# InputDig.net
KiCad netlist of a schematic drawn in Altium Designer
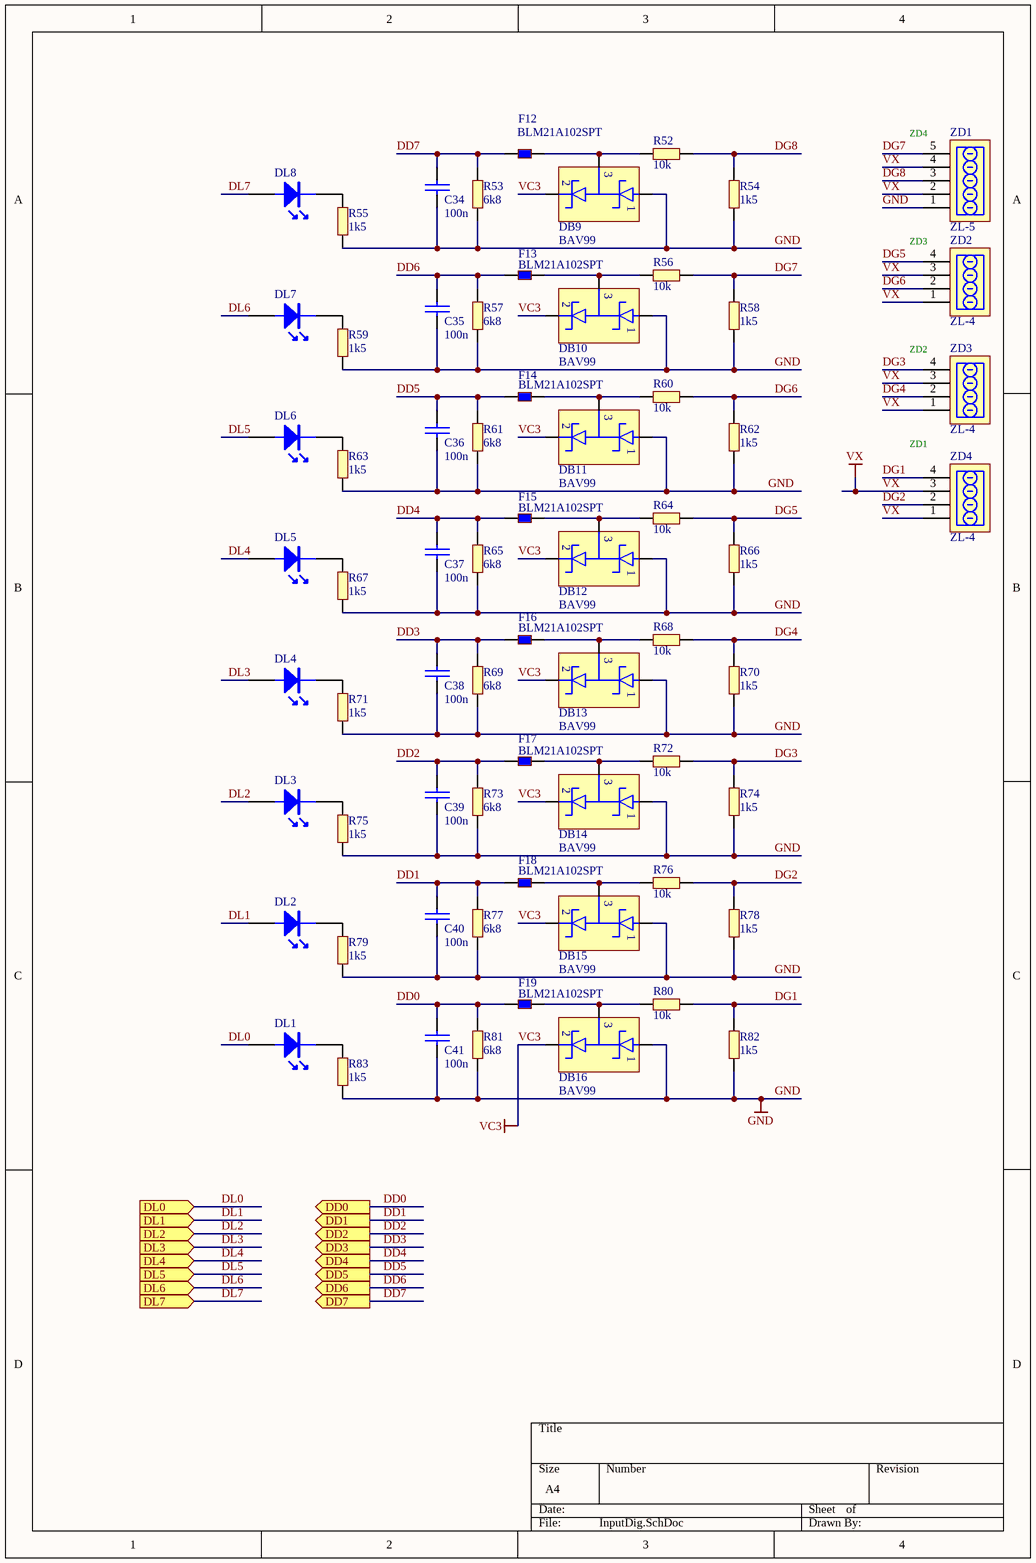
[diagram p0: InputDig.SchDoc]

(export (version "E")
  (design (tool "Eeschema 10.0.6"))
  (components
    (comp (ref "C34")
      (value "100n")
      (footprint "0603C")
      (description "Capacitor")
      (libsource (lib "*") (part "CAP"))
    )
    (comp (ref "C35")
      (value "100n")
      (footprint "0603C")
      (description "Capacitor")
      (libsource (lib "*") (part "CAP"))
    )
    (comp (ref "C36")
      (value "100n")
      (footprint "0603C")
      (description "Capacitor")
      (libsource (lib "*") (part "CAP"))
    )
    (comp (ref "C37")
      (value "100n")
      (footprint "0603C")
      (description "Capacitor")
      (libsource (lib "*") (part "CAP"))
    )
    (comp (ref "C38")
      (value "100n")
      (footprint "0603C")
      (description "Capacitor")
      (libsource (lib "*") (part "CAP"))
    )
    (comp (ref "C39")
      (value "100n")
      (footprint "0603C")
      (description "Capacitor")
      (libsource (lib "*") (part "CAP"))
    )
    (comp (ref "C40")
      (value "100n")
      (footprint "0603C")
      (description "Capacitor")
      (libsource (lib "*") (part "CAP"))
    )
    (comp (ref "C41")
      (value "100n")
      (footprint "0603C")
      (description "Capacitor")
      (libsource (lib "*") (part "CAP"))
    )
    (comp (ref "DB9") (value "BAV99") (footprint "SOT-23") (libsource (lib "*") (part "BAS70-04")))
    (comp (ref "DB10") (value "BAV99") (footprint "SOT-23") (libsource (lib "*") (part "BAS70-04")))
    (comp (ref "DB11") (value "BAV99") (footprint "SOT-23") (libsource (lib "*") (part "BAS70-04")))
    (comp (ref "DB12") (value "BAV99") (footprint "SOT-23") (libsource (lib "*") (part "BAS70-04")))
    (comp (ref "DB13") (value "BAV99") (footprint "SOT-23") (libsource (lib "*") (part "BAS70-04")))
    (comp (ref "DB14") (value "BAV99") (footprint "SOT-23") (libsource (lib "*") (part "BAS70-04")))
    (comp (ref "DB15") (value "BAV99") (footprint "SOT-23") (libsource (lib "*") (part "BAS70-04")))
    (comp (ref "DB16") (value "BAV99") (footprint "SOT-23") (libsource (lib "*") (part "BAS70-04")))
    (comp (ref "DL1") (value "~") (footprint "0603DR") (libsource (lib "*") (part "LED")))
    (comp (ref "DL2") (value "~") (footprint "0603DR") (libsource (lib "*") (part "LED")))
    (comp (ref "DL3") (value "~") (footprint "0603DR") (libsource (lib "*") (part "LED")))
    (comp (ref "DL4") (value "~") (footprint "0603DR") (libsource (lib "*") (part "LED")))
    (comp (ref "DL5") (value "~") (footprint "0603DR") (libsource (lib "*") (part "LED")))
    (comp (ref "DL6") (value "~") (footprint "0603DR") (libsource (lib "*") (part "LED")))
    (comp (ref "DL7") (value "~") (footprint "0603DR") (libsource (lib "*") (part "LED")))
    (comp (ref "DL8") (value "~") (footprint "0603DR") (libsource (lib "*") (part "LED")))
    (comp (ref "F12")
      (value "BLM21A102SPT")
      (footprint "0603L")
      (description "Koralik ferrytowy")
      (libsource (lib "*") (part "KORALIK"))
    )
    (comp (ref "F13")
      (value "BLM21A102SPT")
      (footprint "0603L")
      (description "Koralik ferrytowy")
      (libsource (lib "*") (part "KORALIK"))
    )
    (comp (ref "F14")
      (value "BLM21A102SPT")
      (footprint "0603L")
      (description "Koralik ferrytowy")
      (libsource (lib "*") (part "KORALIK"))
    )
    (comp (ref "F15")
      (value "BLM21A102SPT")
      (footprint "0603L")
      (description "Koralik ferrytowy")
      (libsource (lib "*") (part "KORALIK"))
    )
    (comp (ref "F16")
      (value "BLM21A102SPT")
      (footprint "0603L")
      (description "Koralik ferrytowy")
      (libsource (lib "*") (part "KORALIK"))
    )
    (comp (ref "F17")
      (value "BLM21A102SPT")
      (footprint "0603L")
      (description "Koralik ferrytowy")
      (libsource (lib "*") (part "KORALIK"))
    )
    (comp (ref "F18")
      (value "BLM21A102SPT")
      (footprint "0603L")
      (description "Koralik ferrytowy")
      (libsource (lib "*") (part "KORALIK"))
    )
    (comp (ref "F19")
      (value "BLM21A102SPT")
      (footprint "0603L")
      (description "Koralik ferrytowy")
      (libsource (lib "*") (part "KORALIK"))
    )
    (comp (ref "R52") (value "10k") (footprint "0603R") (libsource (lib "*") (part "RES3")))
    (comp (ref "R53") (value "6k8") (footprint "0603R") (libsource (lib "") (part "RES3_1")))
    (comp (ref "R54") (value "1k5") (footprint "0805R") (libsource (lib "*") (part "RES3")))
    (comp (ref "R55") (value "1k5") (footprint "0603R") (libsource (lib "*") (part "RES3")))
    (comp (ref "R56") (value "10k") (footprint "0603R") (libsource (lib "*") (part "RES3")))
    (comp (ref "R57") (value "6k8") (footprint "0603R") (libsource (lib "") (part "RES3_1")))
    (comp (ref "R58") (value "1k5") (footprint "0805R") (libsource (lib "*") (part "RES3")))
    (comp (ref "R59") (value "1k5") (footprint "0603R") (libsource (lib "*") (part "RES3")))
    (comp (ref "R60") (value "10k") (footprint "0603R") (libsource (lib "*") (part "RES3")))
    (comp (ref "R61") (value "6k8") (footprint "0603R") (libsource (lib "") (part "RES3_1")))
    (comp (ref "R62") (value "1k5") (footprint "0805R") (libsource (lib "*") (part "RES3")))
    (comp (ref "R63") (value "1k5") (footprint "0603R") (libsource (lib "*") (part "RES3")))
    (comp (ref "R64") (value "10k") (footprint "0603R") (libsource (lib "*") (part "RES3")))
    (comp (ref "R65") (value "6k8") (footprint "0603R") (libsource (lib "") (part "RES3_1")))
    (comp (ref "R66") (value "1k5") (footprint "0805R") (libsource (lib "*") (part "RES3")))
    (comp (ref "R67") (value "1k5") (footprint "0603R") (libsource (lib "*") (part "RES3")))
    (comp (ref "R68") (value "10k") (footprint "0603R") (libsource (lib "*") (part "RES3")))
    (comp (ref "R69") (value "6k8") (footprint "0603R") (libsource (lib "") (part "RES3_1")))
    (comp (ref "R70") (value "1k5") (footprint "0805R") (libsource (lib "*") (part "RES3")))
    (comp (ref "R71") (value "1k5") (footprint "0603R") (libsource (lib "*") (part "RES3")))
    (comp (ref "R72") (value "10k") (footprint "0603R") (libsource (lib "*") (part "RES3")))
    (comp (ref "R73") (value "6k8") (footprint "0603R") (libsource (lib "") (part "RES3_1")))
    (comp (ref "R74") (value "1k5") (footprint "0805R") (libsource (lib "*") (part "RES3")))
    (comp (ref "R75") (value "1k5") (footprint "0603R") (libsource (lib "*") (part "RES3")))
    (comp (ref "R76") (value "10k") (footprint "0603R") (libsource (lib "*") (part "RES3")))
    (comp (ref "R77") (value "6k8") (footprint "0603R") (libsource (lib "") (part "RES3_1")))
    (comp (ref "R78") (value "1k5") (footprint "0805R") (libsource (lib "*") (part "RES3")))
    (comp (ref "R79") (value "1k5") (footprint "0603R") (libsource (lib "*") (part "RES3")))
    (comp (ref "R80") (value "10k") (footprint "0603R") (libsource (lib "*") (part "RES3")))
    (comp (ref "R81") (value "6k8") (footprint "0603R") (libsource (lib "") (part "RES3_1")))
    (comp (ref "R82") (value "1k5") (footprint "0805R") (libsource (lib "*") (part "RES3")))
    (comp (ref "R83") (value "1k5") (footprint "0603R") (libsource (lib "*") (part "RES3")))
    (comp (ref "ZD1")
      (value "ZL-5")
      (footprint "ARC-5-3.5-TYCO-2")
      (libsource (lib "ElhosSchLib") (part "ZL-5"))
    )
    (comp (ref "ZD2") (value "ZL-4") (footprint "ARC-4-3.5-TYCO-2") (libsource (lib "*") (part "ZL-4")))
    (comp (ref "ZD3") (value "ZL-4") (footprint "ARC-4-3.5-TYCO-2") (libsource (lib "*") (part "ZL-4")))
    (comp (ref "ZD4") (value "ZL-4") (footprint "ARC-4-3.5-TYCO-2") (libsource (lib "*") (part "ZL-4")))
  )
  (nets
    (net (code "1") (name "/DD0") (class "Default")
      (node (ref "C41") (pin "1") (pinfunction "1_1") (pintype "passive"))
      (node (ref "F19") (pin "1") (pintype "passive"))
      (node (ref "R81") (pin "1") (pintype "passive"))
    )
    (net (code "2") (name "/DD1") (class "Default")
      (node (ref "C40") (pin "1") (pinfunction "1_1") (pintype "passive"))
      (node (ref "F18") (pin "1") (pintype "passive"))
      (node (ref "R77") (pin "1") (pintype "passive"))
    )
    (net (code "3") (name "/DD2") (class "Default")
      (node (ref "C39") (pin "1") (pinfunction "1_1") (pintype "passive"))
      (node (ref "F17") (pin "1") (pintype "passive"))
      (node (ref "R73") (pin "1") (pintype "passive"))
    )
    (net (code "4") (name "/DD3") (class "Default")
      (node (ref "C38") (pin "1") (pinfunction "1_1") (pintype "passive"))
      (node (ref "F16") (pin "1") (pintype "passive"))
      (node (ref "R69") (pin "1") (pintype "passive"))
    )
    (net (code "5") (name "/DD4") (class "Default")
      (node (ref "C37") (pin "1") (pinfunction "1_1") (pintype "passive"))
      (node (ref "F15") (pin "1") (pintype "passive"))
      (node (ref "R65") (pin "1") (pintype "passive"))
    )
    (net (code "6") (name "/DD5") (class "Default")
      (node (ref "C36") (pin "1") (pinfunction "1_1") (pintype "passive"))
      (node (ref "F14") (pin "1") (pintype "passive"))
      (node (ref "R61") (pin "1") (pintype "passive"))
    )
    (net (code "7") (name "/DD6") (class "Default")
      (node (ref "C35") (pin "1") (pinfunction "1_1") (pintype "passive"))
      (node (ref "F13") (pin "1") (pintype "passive"))
      (node (ref "R57") (pin "1") (pintype "passive"))
    )
    (net (code "8") (name "/DD7") (class "Default")
      (node (ref "C34") (pin "1") (pinfunction "1_1") (pintype "passive"))
      (node (ref "F12") (pin "1") (pintype "passive"))
      (node (ref "R53") (pin "1") (pintype "passive"))
    )
    (net (code "9") (name "/DG1") (class "Default")
      (node (ref "R80") (pin "1") (pintype "passive"))
      (node (ref "R82") (pin "1") (pintype "passive"))
      (node (ref "ZD4") (pin "4") (pintype "passive"))
    )
    (net (code "10") (name "/DG2") (class "Default")
      (node (ref "R76") (pin "1") (pintype "passive"))
      (node (ref "R78") (pin "1") (pintype "passive"))
      (node (ref "ZD4") (pin "2") (pintype "passive"))
    )
    (net (code "11") (name "/DG3") (class "Default")
      (node (ref "R72") (pin "1") (pintype "passive"))
      (node (ref "R74") (pin "1") (pintype "passive"))
      (node (ref "ZD3") (pin "4") (pintype "passive"))
    )
    (net (code "12") (name "/DG4") (class "Default")
      (node (ref "R68") (pin "1") (pintype "passive"))
      (node (ref "R70") (pin "1") (pintype "passive"))
      (node (ref "ZD3") (pin "2") (pintype "passive"))
    )
    (net (code "13") (name "/DG5") (class "Default")
      (node (ref "R64") (pin "1") (pintype "passive"))
      (node (ref "R66") (pin "1") (pintype "passive"))
      (node (ref "ZD2") (pin "4") (pintype "passive"))
    )
    (net (code "14") (name "/DG6") (class "Default")
      (node (ref "R60") (pin "1") (pintype "passive"))
      (node (ref "R62") (pin "1") (pintype "passive"))
      (node (ref "ZD2") (pin "2") (pintype "passive"))
    )
    (net (code "15") (name "/DG7") (class "Default")
      (node (ref "R56") (pin "1") (pintype "passive"))
      (node (ref "R58") (pin "1") (pintype "passive"))
      (node (ref "ZD1") (pin "5") (pintype "passive"))
    )
    (net (code "16") (name "/DG8") (class "Default")
      (node (ref "R52") (pin "1") (pintype "passive"))
      (node (ref "R54") (pin "1") (pintype "passive"))
      (node (ref "ZD1") (pin "3") (pintype "passive"))
    )
    (net (code "17") (name "/DL0") (class "Default")
      (node (ref "DL1") (pin "A") (pinfunction "1_A") (pintype "passive"))
    )
    (net (code "18") (name "/DL1") (class "Default")
      (node (ref "DL2") (pin "A") (pinfunction "1_A") (pintype "passive"))
    )
    (net (code "19") (name "/DL2") (class "Default")
      (node (ref "DL3") (pin "A") (pinfunction "1_A") (pintype "passive"))
    )
    (net (code "20") (name "/DL3") (class "Default")
      (node (ref "DL4") (pin "A") (pinfunction "1_A") (pintype "passive"))
    )
    (net (code "21") (name "/DL4") (class "Default")
      (node (ref "DL5") (pin "A") (pinfunction "1_A") (pintype "passive"))
    )
    (net (code "22") (name "/DL5") (class "Default")
      (node (ref "DL6") (pin "A") (pinfunction "1_A") (pintype "passive"))
    )
    (net (code "23") (name "/DL6") (class "Default")
      (node (ref "DL7") (pin "A") (pinfunction "1_A") (pintype "passive"))
    )
    (net (code "24") (name "/DL7") (class "Default")
      (node (ref "DL8") (pin "A") (pinfunction "1_A") (pintype "passive"))
    )
    (net (code "25") (name "GND") (class "Default")
      (node (ref "C34") (pin "2") (pinfunction "2_2") (pintype "passive"))
      (node (ref "C35") (pin "2") (pinfunction "2_2") (pintype "passive"))
      (node (ref "C36") (pin "2") (pinfunction "2_2") (pintype "passive"))
      (node (ref "C37") (pin "2") (pinfunction "2_2") (pintype "passive"))
      (node (ref "C38") (pin "2") (pinfunction "2_2") (pintype "passive"))
      (node (ref "C39") (pin "2") (pinfunction "2_2") (pintype "passive"))
      (node (ref "C40") (pin "2") (pinfunction "2_2") (pintype "passive"))
      (node (ref "C41") (pin "2") (pinfunction "2_2") (pintype "passive"))
      (node (ref "DB10") (pin "1") (pintype "passive"))
      (node (ref "DB11") (pin "1") (pintype "passive"))
      (node (ref "DB12") (pin "1") (pintype "passive"))
      (node (ref "DB13") (pin "1") (pintype "passive"))
      (node (ref "DB14") (pin "1") (pintype "passive"))
      (node (ref "DB15") (pin "1") (pintype "passive"))
      (node (ref "DB16") (pin "1") (pintype "passive"))
      (node (ref "DB9") (pin "1") (pintype "passive"))
      (node (ref "R53") (pin "2") (pintype "passive"))
      (node (ref "R54") (pin "2") (pintype "passive"))
      (node (ref "R55") (pin "2") (pintype "passive"))
      (node (ref "R57") (pin "2") (pintype "passive"))
      (node (ref "R58") (pin "2") (pintype "passive"))
      (node (ref "R59") (pin "2") (pintype "passive"))
      (node (ref "R61") (pin "2") (pintype "passive"))
      (node (ref "R62") (pin "2") (pintype "passive"))
      (node (ref "R63") (pin "2") (pintype "passive"))
      (node (ref "R65") (pin "2") (pintype "passive"))
      (node (ref "R66") (pin "2") (pintype "passive"))
      (node (ref "R67") (pin "2") (pintype "passive"))
      (node (ref "R69") (pin "2") (pintype "passive"))
      (node (ref "R70") (pin "2") (pintype "passive"))
      (node (ref "R71") (pin "2") (pintype "passive"))
      (node (ref "R73") (pin "2") (pintype "passive"))
      (node (ref "R74") (pin "2") (pintype "passive"))
      (node (ref "R75") (pin "2") (pintype "passive"))
      (node (ref "R77") (pin "2") (pintype "passive"))
      (node (ref "R78") (pin "2") (pintype "passive"))
      (node (ref "R79") (pin "2") (pintype "passive"))
      (node (ref "R81") (pin "2") (pintype "passive"))
      (node (ref "R82") (pin "2") (pintype "passive"))
      (node (ref "R83") (pin "2") (pintype "passive"))
      (node (ref "ZD1") (pin "1") (pintype "passive"))
    )
    (net (code "26") (name "Net-(DB9-Pad3)") (class "Default")
      (node (ref "DB9") (pin "3") (pintype "passive"))
      (node (ref "F12") (pin "2") (pintype "passive"))
      (node (ref "R52") (pin "2") (pintype "passive"))
    )
    (net (code "27") (name "Net-(DB10-Pad3)") (class "Default")
      (node (ref "DB10") (pin "3") (pintype "passive"))
      (node (ref "F13") (pin "2") (pintype "passive"))
      (node (ref "R56") (pin "2") (pintype "passive"))
    )
    (net (code "28") (name "Net-(DB11-Pad3)") (class "Default")
      (node (ref "DB11") (pin "3") (pintype "passive"))
      (node (ref "F14") (pin "2") (pintype "passive"))
      (node (ref "R60") (pin "2") (pintype "passive"))
    )
    (net (code "29") (name "Net-(DB12-Pad3)") (class "Default")
      (node (ref "DB12") (pin "3") (pintype "passive"))
      (node (ref "F15") (pin "2") (pintype "passive"))
      (node (ref "R64") (pin "2") (pintype "passive"))
    )
    (net (code "30") (name "Net-(DB13-Pad3)") (class "Default")
      (node (ref "DB13") (pin "3") (pintype "passive"))
      (node (ref "F16") (pin "2") (pintype "passive"))
      (node (ref "R68") (pin "2") (pintype "passive"))
    )
    (net (code "31") (name "Net-(DB14-Pad3)") (class "Default")
      (node (ref "DB14") (pin "3") (pintype "passive"))
      (node (ref "F17") (pin "2") (pintype "passive"))
      (node (ref "R72") (pin "2") (pintype "passive"))
    )
    (net (code "32") (name "Net-(DB15-Pad3)") (class "Default")
      (node (ref "DB15") (pin "3") (pintype "passive"))
      (node (ref "F18") (pin "2") (pintype "passive"))
      (node (ref "R76") (pin "2") (pintype "passive"))
    )
    (net (code "33") (name "Net-(DB16-Pad3)") (class "Default")
      (node (ref "DB16") (pin "3") (pintype "passive"))
      (node (ref "F19") (pin "2") (pintype "passive"))
      (node (ref "R80") (pin "2") (pintype "passive"))
    )
    (net (code "34") (name "Net-(DL1-2)") (class "Default")
      (node (ref "DL1") (pin "K") (pinfunction "2_K") (pintype "passive"))
      (node (ref "R83") (pin "1") (pintype "passive"))
    )
    (net (code "35") (name "Net-(DL2-2)") (class "Default")
      (node (ref "DL2") (pin "K") (pinfunction "2_K") (pintype "passive"))
      (node (ref "R79") (pin "1") (pintype "passive"))
    )
    (net (code "36") (name "Net-(DL3-2)") (class "Default")
      (node (ref "DL3") (pin "K") (pinfunction "2_K") (pintype "passive"))
      (node (ref "R75") (pin "1") (pintype "passive"))
    )
    (net (code "37") (name "Net-(DL4-2)") (class "Default")
      (node (ref "DL4") (pin "K") (pinfunction "2_K") (pintype "passive"))
      (node (ref "R71") (pin "1") (pintype "passive"))
    )
    (net (code "38") (name "Net-(DL5-2)") (class "Default")
      (node (ref "DL5") (pin "K") (pinfunction "2_K") (pintype "passive"))
      (node (ref "R67") (pin "1") (pintype "passive"))
    )
    (net (code "39") (name "Net-(DL6-2)") (class "Default")
      (node (ref "DL6") (pin "K") (pinfunction "2_K") (pintype "passive"))
      (node (ref "R63") (pin "1") (pintype "passive"))
    )
    (net (code "40") (name "Net-(DL7-2)") (class "Default")
      (node (ref "DL7") (pin "K") (pinfunction "2_K") (pintype "passive"))
      (node (ref "R59") (pin "1") (pintype "passive"))
    )
    (net (code "41") (name "Net-(DL8-2)") (class "Default")
      (node (ref "DL8") (pin "K") (pinfunction "2_K") (pintype "passive"))
      (node (ref "R55") (pin "1") (pintype "passive"))
    )
    (net (code "42") (name "VC3") (class "Default")
      (node (ref "DB10") (pin "2") (pintype "passive"))
      (node (ref "DB11") (pin "2") (pintype "passive"))
      (node (ref "DB12") (pin "2") (pintype "passive"))
      (node (ref "DB13") (pin "2") (pintype "passive"))
      (node (ref "DB14") (pin "2") (pintype "passive"))
      (node (ref "DB15") (pin "2") (pintype "passive"))
      (node (ref "DB16") (pin "2") (pintype "passive"))
      (node (ref "DB9") (pin "2") (pintype "passive"))
    )
    (net (code "43") (name "VX") (class "Default")
      (node (ref "ZD1") (pin "2") (pintype "passive"))
      (node (ref "ZD1") (pin "4") (pintype "passive"))
      (node (ref "ZD2") (pin "1") (pintype "passive"))
      (node (ref "ZD2") (pin "3") (pintype "passive"))
      (node (ref "ZD3") (pin "1") (pintype "passive"))
      (node (ref "ZD3") (pin "3") (pintype "passive"))
      (node (ref "ZD4") (pin "1") (pintype "passive"))
      (node (ref "ZD4") (pin "3") (pintype "passive"))
    )
  )
)
